# W024.net
KiCad netlist of a schematic drawn in EAGLE
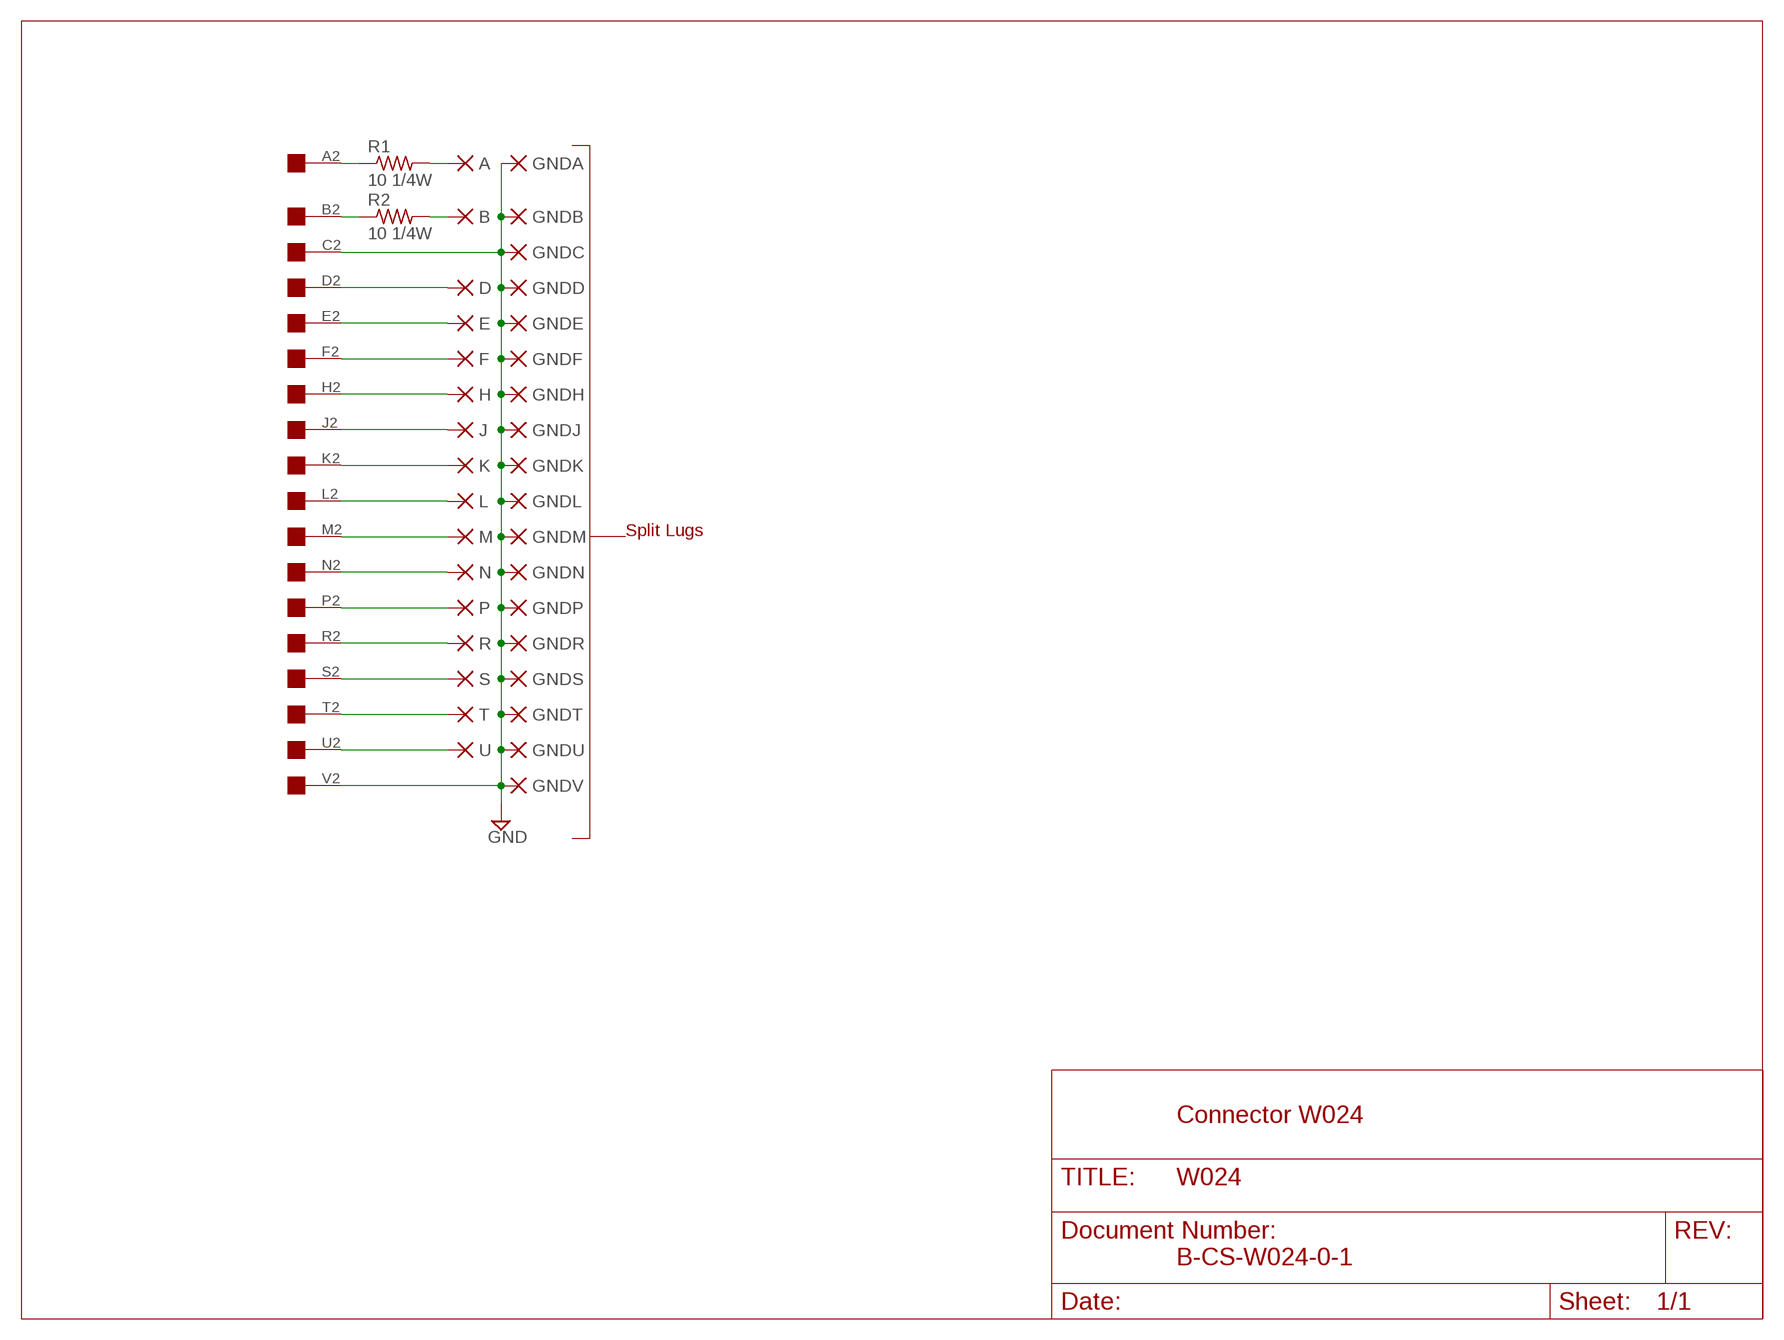
[diagram p0: schematic, sheet 1]

(export (version "E")
  (design (tool "Eeschema 10.0.6"))
  (components
    (comp (ref "A")
      (value "PAD-0465")
      (footprint "eagle-import:0465")
      (libsource (lib "eagle-import") (part "PAD-0465"))
    )
    (comp (ref "B")
      (value "PAD-0465")
      (footprint "eagle-import:0465")
      (libsource (lib "eagle-import") (part "PAD-0465"))
    )
    (comp (ref "D")
      (value "PAD-0465")
      (footprint "eagle-import:0465")
      (libsource (lib "eagle-import") (part "PAD-0465"))
    )
    (comp (ref "E")
      (value "PAD-0465")
      (footprint "eagle-import:0465")
      (libsource (lib "eagle-import") (part "PAD-0465"))
    )
    (comp (ref "F")
      (value "PAD-0465")
      (footprint "eagle-import:0465")
      (libsource (lib "eagle-import") (part "PAD-0465"))
    )
    (comp (ref "GNDA")
      (value "PAD-0465")
      (footprint "eagle-import:0465")
      (libsource (lib "eagle-import") (part "PAD-0465"))
    )
    (comp (ref "GNDB")
      (value "PAD-0465")
      (footprint "eagle-import:0465")
      (libsource (lib "eagle-import") (part "PAD-0465"))
    )
    (comp (ref "GNDC")
      (value "PAD-0465")
      (footprint "eagle-import:0465")
      (libsource (lib "eagle-import") (part "PAD-0465"))
    )
    (comp (ref "GNDD")
      (value "PAD-0465")
      (footprint "eagle-import:0465")
      (libsource (lib "eagle-import") (part "PAD-0465"))
    )
    (comp (ref "GNDE")
      (value "PAD-0465")
      (footprint "eagle-import:0465")
      (libsource (lib "eagle-import") (part "PAD-0465"))
    )
    (comp (ref "GNDF")
      (value "PAD-0465")
      (footprint "eagle-import:0465")
      (libsource (lib "eagle-import") (part "PAD-0465"))
    )
    (comp (ref "GNDH")
      (value "PAD-0465")
      (footprint "eagle-import:0465")
      (libsource (lib "eagle-import") (part "PAD-0465"))
    )
    (comp (ref "GNDJ")
      (value "PAD-0465")
      (footprint "eagle-import:0465")
      (libsource (lib "eagle-import") (part "PAD-0465"))
    )
    (comp (ref "GNDK")
      (value "PAD-0465")
      (footprint "eagle-import:0465")
      (libsource (lib "eagle-import") (part "PAD-0465"))
    )
    (comp (ref "GNDL")
      (value "PAD-0465")
      (footprint "eagle-import:0465")
      (libsource (lib "eagle-import") (part "PAD-0465"))
    )
    (comp (ref "GNDM")
      (value "PAD-0465")
      (footprint "eagle-import:0465")
      (libsource (lib "eagle-import") (part "PAD-0465"))
    )
    (comp (ref "GNDN")
      (value "PAD-0465")
      (footprint "eagle-import:0465")
      (libsource (lib "eagle-import") (part "PAD-0465"))
    )
    (comp (ref "GNDP")
      (value "PAD-0465")
      (footprint "eagle-import:0465")
      (libsource (lib "eagle-import") (part "PAD-0465"))
    )
    (comp (ref "GNDR")
      (value "PAD-0465")
      (footprint "eagle-import:0465")
      (libsource (lib "eagle-import") (part "PAD-0465"))
    )
    (comp (ref "GNDS")
      (value "PAD-0465")
      (footprint "eagle-import:0465")
      (libsource (lib "eagle-import") (part "PAD-0465"))
    )
    (comp (ref "GNDT")
      (value "PAD-0465")
      (footprint "eagle-import:0465")
      (libsource (lib "eagle-import") (part "PAD-0465"))
    )
    (comp (ref "GNDU")
      (value "PAD-0465")
      (footprint "eagle-import:0465")
      (libsource (lib "eagle-import") (part "PAD-0465"))
    )
    (comp (ref "GNDV")
      (value "PAD-0465")
      (footprint "eagle-import:0465")
      (libsource (lib "eagle-import") (part "PAD-0465"))
    )
    (comp (ref "H")
      (value "PAD-0465")
      (footprint "eagle-import:0465")
      (libsource (lib "eagle-import") (part "PAD-0465"))
    )
    (comp (ref "J")
      (value "PAD-0465")
      (footprint "eagle-import:0465")
      (libsource (lib "eagle-import") (part "PAD-0465"))
    )
    (comp (ref "K")
      (value "PAD-0465")
      (footprint "eagle-import:0465")
      (libsource (lib "eagle-import") (part "PAD-0465"))
    )
    (comp (ref "L")
      (value "PAD-0465")
      (footprint "eagle-import:0465")
      (libsource (lib "eagle-import") (part "PAD-0465"))
    )
    (comp (ref "M")
      (value "PAD-0465")
      (footprint "eagle-import:0465")
      (libsource (lib "eagle-import") (part "PAD-0465"))
    )
    (comp (ref "N")
      (value "PAD-0465")
      (footprint "eagle-import:0465")
      (libsource (lib "eagle-import") (part "PAD-0465"))
    )
    (comp (ref "P")
      (value "PAD-0465")
      (footprint "eagle-import:0465")
      (libsource (lib "eagle-import") (part "PAD-0465"))
    )
    (comp (ref "R")
      (value "PAD-0465")
      (footprint "eagle-import:0465")
      (libsource (lib "eagle-import") (part "PAD-0465"))
    )
    (comp (ref "R1")
      (value "10 1/4W")
      (footprint "eagle-import:0207_10")
      (libsource (lib "eagle-import") (part "R-US_0207/10"))
    )
    (comp (ref "R2")
      (value "10 1/4W")
      (footprint "eagle-import:0207_10")
      (libsource (lib "eagle-import") (part "R-US_0207/10"))
    )
    (comp (ref "S")
      (value "PAD-0465")
      (footprint "eagle-import:0465")
      (libsource (lib "eagle-import") (part "PAD-0465"))
    )
    (comp (ref "T")
      (value "PAD-0465")
      (footprint "eagle-import:0465")
      (libsource (lib "eagle-import") (part "PAD-0465"))
    )
    (comp (ref "U")
      (value "PAD-0465")
      (footprint "eagle-import:0465")
      (libsource (lib "eagle-import") (part "PAD-0465"))
    )
    (comp (ref "U$2")
      (value "EDGE-1")
      (footprint "eagle-import:EDGE-CON1")
      (libsource (lib "eagle-import") (part "EDGE-1"))
    )
  )
  (nets
    (net (code "1") (name "GND") (class "Default")
      (node (ref "GNDA") (pin "P$1") (pinfunction "P_P$1") (pintype "passive"))
      (node (ref "GNDB") (pin "P$1") (pinfunction "P_P$1") (pintype "passive"))
      (node (ref "GNDC") (pin "P$1") (pinfunction "P_P$1") (pintype "passive"))
      (node (ref "GNDD") (pin "P$1") (pinfunction "P_P$1") (pintype "passive"))
      (node (ref "GNDE") (pin "P$1") (pinfunction "P_P$1") (pintype "passive"))
      (node (ref "GNDF") (pin "P$1") (pinfunction "P_P$1") (pintype "passive"))
      (node (ref "GNDH") (pin "P$1") (pinfunction "P_P$1") (pintype "passive"))
      (node (ref "GNDJ") (pin "P$1") (pinfunction "P_P$1") (pintype "passive"))
      (node (ref "GNDK") (pin "P$1") (pinfunction "P_P$1") (pintype "passive"))
      (node (ref "GNDL") (pin "P$1") (pinfunction "P_P$1") (pintype "passive"))
      (node (ref "GNDM") (pin "P$1") (pinfunction "P_P$1") (pintype "passive"))
      (node (ref "GNDN") (pin "P$1") (pinfunction "P_P$1") (pintype "passive"))
      (node (ref "GNDP") (pin "P$1") (pinfunction "P_P$1") (pintype "passive"))
      (node (ref "GNDR") (pin "P$1") (pinfunction "P_P$1") (pintype "passive"))
      (node (ref "GNDS") (pin "P$1") (pinfunction "P_P$1") (pintype "passive"))
      (node (ref "GNDT") (pin "P$1") (pinfunction "P_P$1") (pintype "passive"))
      (node (ref "GNDU") (pin "P$1") (pinfunction "P_P$1") (pintype "passive"))
      (node (ref "GNDV") (pin "P$1") (pinfunction "P_P$1") (pintype "passive"))
      (node (ref "U$2") (pin "C2") (pinfunction "1_C2") (pintype "bidirectional"))
      (node (ref "U$2") (pin "V2") (pinfunction "1_V2") (pintype "bidirectional"))
    )
    (net (code "2") (name "Net-(A-P)") (class "Default")
      (node (ref "A") (pin "P$1") (pinfunction "P_P$1") (pintype "passive"))
      (node (ref "R1") (pin "2") (pinfunction "2_2") (pintype "passive"))
    )
    (net (code "3") (name "Net-(B-P)") (class "Default")
      (node (ref "B") (pin "P$1") (pinfunction "P_P$1") (pintype "passive"))
      (node (ref "R2") (pin "2") (pinfunction "2_2") (pintype "passive"))
    )
    (net (code "4") (name "Net-(D-P)") (class "Default")
      (node (ref "D") (pin "P$1") (pinfunction "P_P$1") (pintype "passive"))
      (node (ref "U$2") (pin "D2") (pinfunction "1_D2") (pintype "bidirectional"))
    )
    (net (code "5") (name "Net-(E-P)") (class "Default")
      (node (ref "E") (pin "P$1") (pinfunction "P_P$1") (pintype "passive"))
      (node (ref "U$2") (pin "E2") (pinfunction "1_E2") (pintype "bidirectional"))
    )
    (net (code "6") (name "Net-(F-P)") (class "Default")
      (node (ref "F") (pin "P$1") (pinfunction "P_P$1") (pintype "passive"))
      (node (ref "U$2") (pin "F2") (pinfunction "1_F2") (pintype "bidirectional"))
    )
    (net (code "7") (name "Net-(H-P)") (class "Default")
      (node (ref "H") (pin "P$1") (pinfunction "P_P$1") (pintype "passive"))
      (node (ref "U$2") (pin "H2") (pinfunction "1_H2") (pintype "bidirectional"))
    )
    (net (code "8") (name "Net-(J-P)") (class "Default")
      (node (ref "J") (pin "P$1") (pinfunction "P_P$1") (pintype "passive"))
      (node (ref "U$2") (pin "J2") (pinfunction "1_J2") (pintype "bidirectional"))
    )
    (net (code "9") (name "Net-(K-P)") (class "Default")
      (node (ref "K") (pin "P$1") (pinfunction "P_P$1") (pintype "passive"))
      (node (ref "U$2") (pin "K2") (pinfunction "1_K2") (pintype "bidirectional"))
    )
    (net (code "10") (name "Net-(L-P)") (class "Default")
      (node (ref "L") (pin "P$1") (pinfunction "P_P$1") (pintype "passive"))
      (node (ref "U$2") (pin "L2") (pinfunction "1_L2") (pintype "bidirectional"))
    )
    (net (code "11") (name "Net-(M-P)") (class "Default")
      (node (ref "M") (pin "P$1") (pinfunction "P_P$1") (pintype "passive"))
      (node (ref "U$2") (pin "M2") (pinfunction "1_M2") (pintype "bidirectional"))
    )
    (net (code "12") (name "Net-(N-P)") (class "Default")
      (node (ref "N") (pin "P$1") (pinfunction "P_P$1") (pintype "passive"))
      (node (ref "U$2") (pin "N2") (pinfunction "1_N2") (pintype "bidirectional"))
    )
    (net (code "13") (name "Net-(P-P)") (class "Default")
      (node (ref "P") (pin "P$1") (pinfunction "P_P$1") (pintype "passive"))
      (node (ref "U$2") (pin "P2") (pinfunction "1_P2") (pintype "bidirectional"))
    )
    (net (code "14") (name "Net-(R-P)") (class "Default")
      (node (ref "R") (pin "P$1") (pinfunction "P_P$1") (pintype "passive"))
      (node (ref "U$2") (pin "R2") (pinfunction "1_R2") (pintype "bidirectional"))
    )
    (net (code "15") (name "Net-(S-P)") (class "Default")
      (node (ref "S") (pin "P$1") (pinfunction "P_P$1") (pintype "passive"))
      (node (ref "U$2") (pin "S2") (pinfunction "1_S2") (pintype "bidirectional"))
    )
    (net (code "16") (name "Net-(T-P)") (class "Default")
      (node (ref "T") (pin "P$1") (pinfunction "P_P$1") (pintype "passive"))
      (node (ref "U$2") (pin "T2") (pinfunction "1_T2") (pintype "bidirectional"))
    )
    (net (code "17") (name "Net-(U$2A-1)") (class "Default")
      (node (ref "R1") (pin "1") (pinfunction "1_1") (pintype "passive"))
      (node (ref "U$2") (pin "A2") (pinfunction "1_A2") (pintype "bidirectional"))
    )
    (net (code "18") (name "Net-(U$2B-1)") (class "Default")
      (node (ref "R2") (pin "1") (pinfunction "1_1") (pintype "passive"))
      (node (ref "U$2") (pin "B2") (pinfunction "1_B2") (pintype "bidirectional"))
    )
    (net (code "19") (name "Net-(U$2Q-1)") (class "Default")
      (node (ref "U") (pin "P$1") (pinfunction "P_P$1") (pintype "passive"))
      (node (ref "U$2") (pin "U2") (pinfunction "1_U2") (pintype "bidirectional"))
    )
  )
)
